# design.net
KiCad netlist of a schematic drawn in Altium Designer
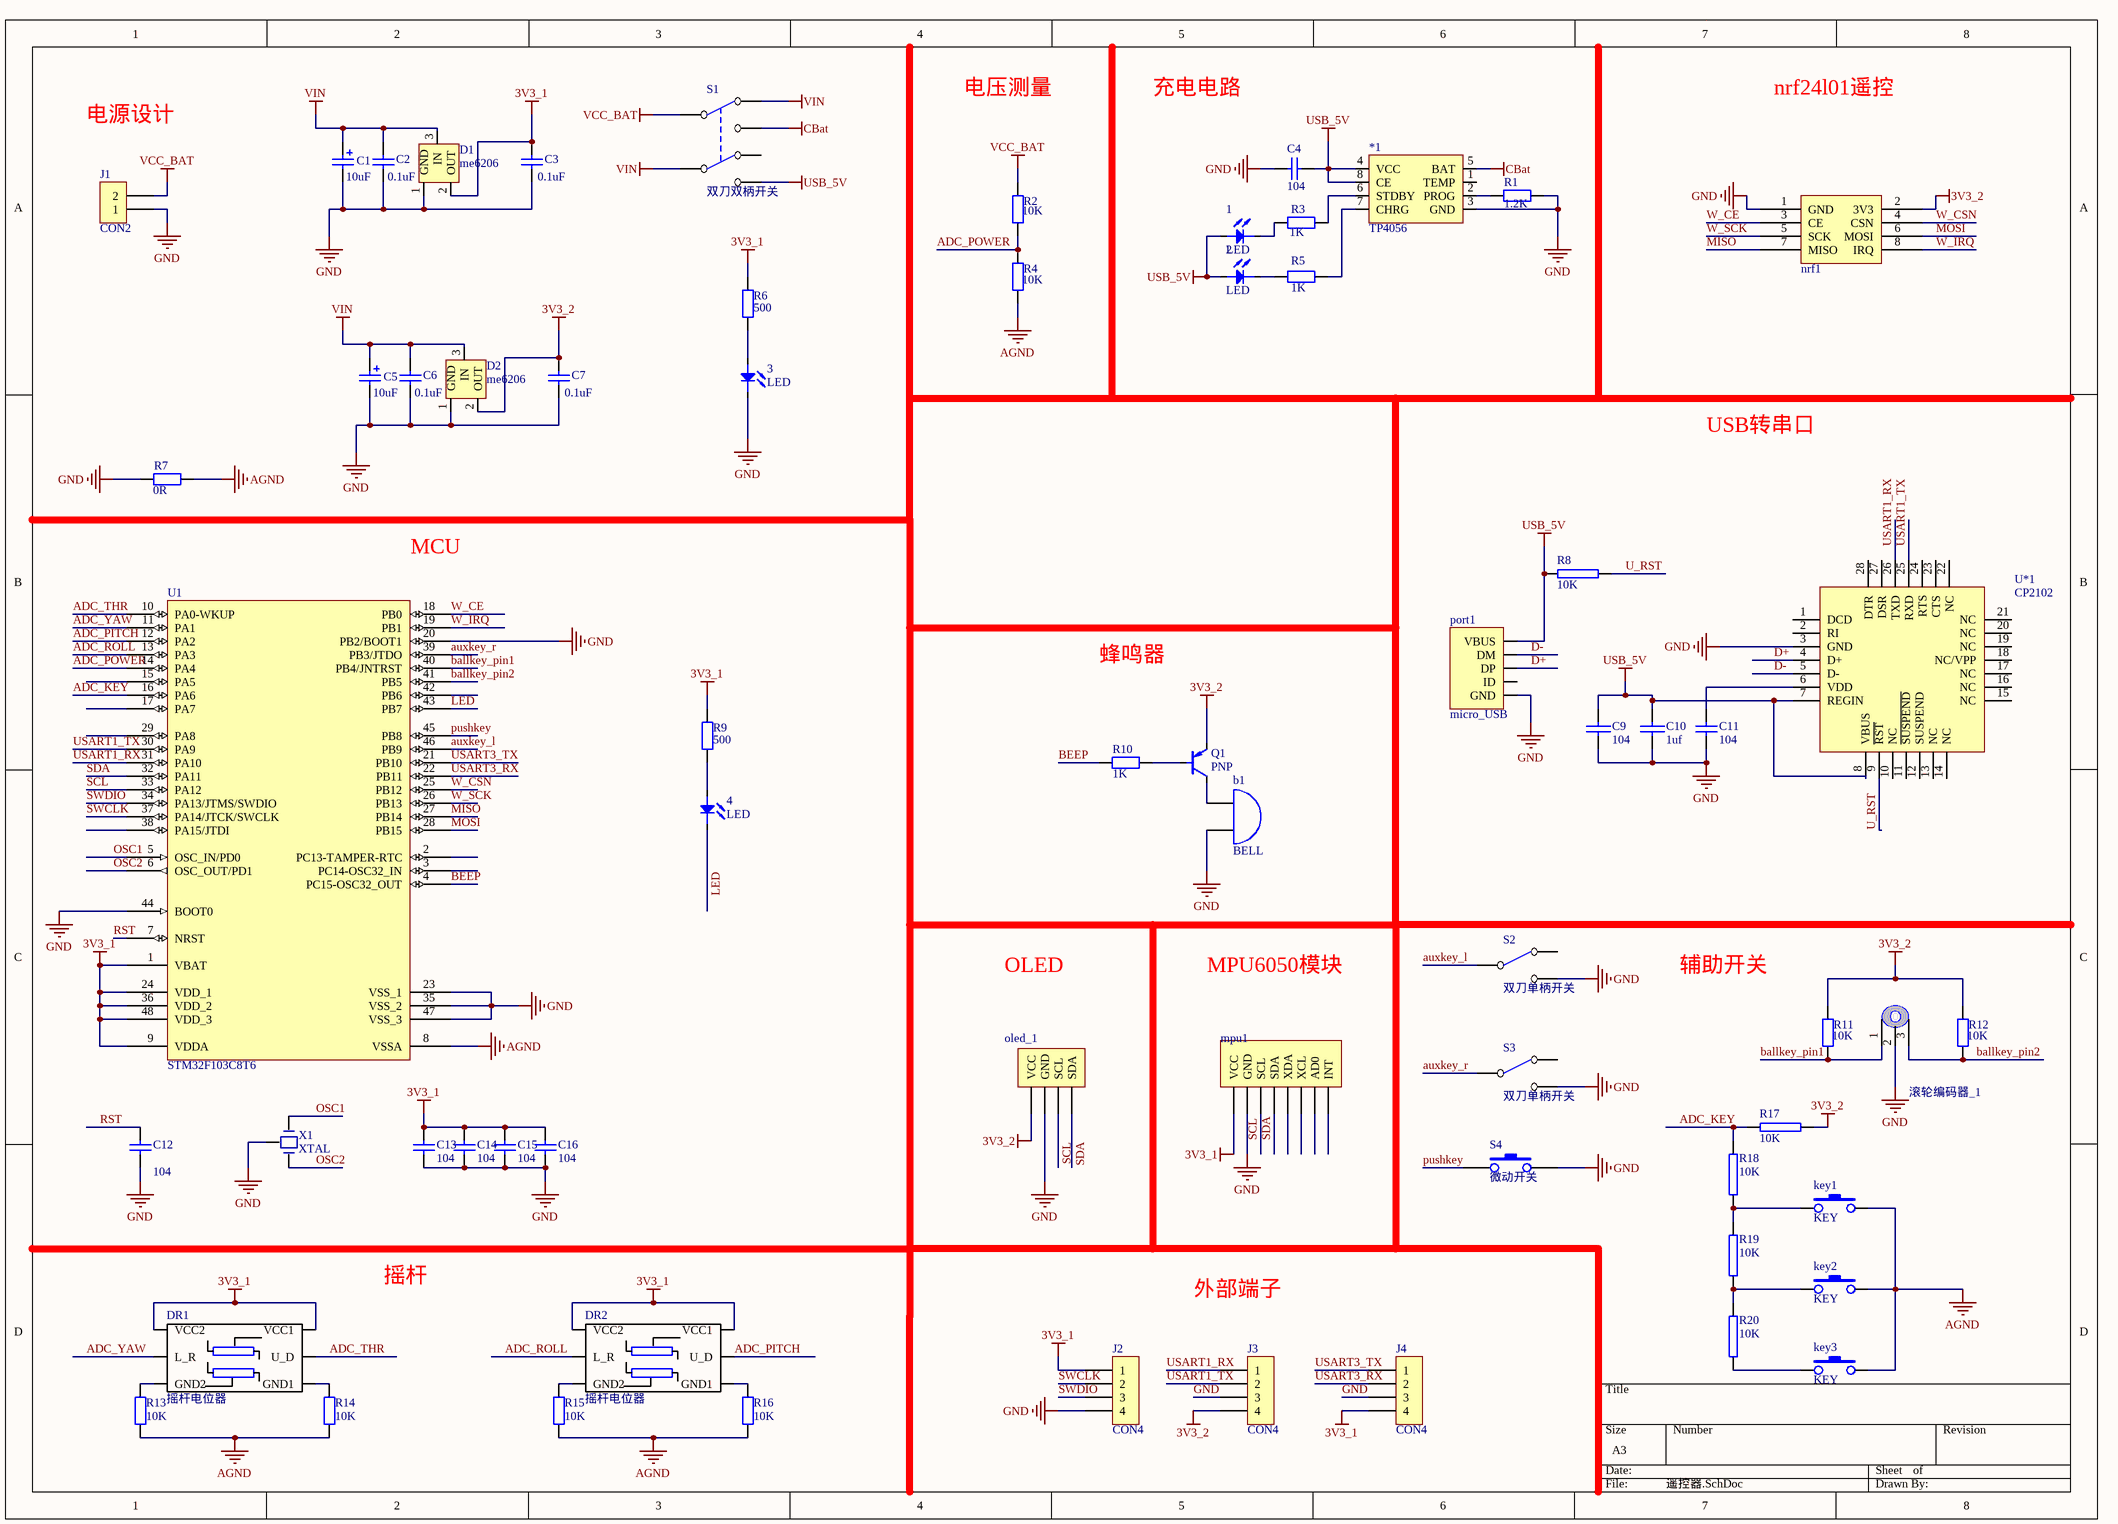
[diagram p0: 遥控器.SchDoc]

(export (version "E")
  (design (tool "Eeschema 10.0.6"))
  (components
    (comp (ref "*1") (value "TP4056") (footprint "LC-SOP-8_EP_150mil") (libsource (lib "my") (part "TP4056")))
    (comp (ref "1") (value "LED") (footprint "LC-0603_LED_S3") (libsource (lib "常用元件库") (part "LED")))
    (comp (ref "2") (value "LED") (footprint "LC-0603_LED_S3") (libsource (lib "常用元件库") (part "LED")))
    (comp (ref "3") (value "LED") (footprint "LC-0603_LED_S3") (libsource (lib "常用元件库") (part "LED")))
    (comp (ref "4") (value "LED") (footprint "LC-0603_LED_S3") (libsource (lib "常用元件库") (part "LED")))
    (comp (ref "b1") (value "BELL") (footprint "bell_d5") (libsource (lib "常用元件库") (part "BELL")))
    (comp (ref "C1")
      (value "10uF")
      (footprint "LC-0603_C")
      (description "Polarized Capacitor (Axial)")
      (fields (field (name "Comment") "Cap Pol2") (field (name "PUBLISHER") "Altium Limited"))
      (libsource (lib "Miscellaneous Devices") (part "Cap Pol2"))
    )
    (comp (ref "C2")
      (value "0.1uF")
      (footprint "LC-0603_C")
      (description "Capacitor")
      (fields (field (name "Comment") "Cap") (field (name "PUBLISHER") "Altium Limited"))
      (libsource (lib "Miscellaneous Devices") (part "Cap"))
    )
    (comp (ref "C3")
      (value "0.1uF")
      (footprint "LC-0603_C")
      (description "Capacitor")
      (fields (field (name "Comment") "Cap") (field (name "PUBLISHER") "Altium Limited"))
      (libsource (lib "Miscellaneous Devices") (part "Cap"))
    )
    (comp (ref "C4")
      (value "104")
      (footprint "LC-0603_C")
      (description "Capacitor")
      (fields (field (name "Comment") "Cap") (field (name "PUBLISHER") "Altium Limited"))
      (libsource (lib "Miscellaneous Devices") (part "Cap"))
    )
    (comp (ref "C5")
      (value "10uF")
      (footprint "LC-0603_C")
      (description "Polarized Capacitor (Axial)")
      (fields (field (name "Comment") "Cap Pol2") (field (name "PUBLISHER") "Altium Limited"))
      (libsource (lib "Miscellaneous Devices") (part "Cap Pol2"))
    )
    (comp (ref "C6")
      (value "0.1uF")
      (footprint "LC-0603_C")
      (description "Capacitor")
      (fields (field (name "Comment") "Cap") (field (name "PUBLISHER") "Altium Limited"))
      (libsource (lib "Miscellaneous Devices") (part "Cap"))
    )
    (comp (ref "C7")
      (value "0.1uF")
      (footprint "LC-0603_C")
      (description "Capacitor")
      (fields (field (name "Comment") "Cap") (field (name "PUBLISHER") "Altium Limited"))
      (libsource (lib "Miscellaneous Devices") (part "Cap"))
    )
    (comp (ref "C9") (value "104") (footprint "LC-0603_C") (libsource (lib "常用元件库") (part "CAP")))
    (comp (ref "C10") (value "1uf") (footprint "LC-0603_C") (libsource (lib "常用元件库") (part "CAP")))
    (comp (ref "C11")
      (value "104")
      (footprint "LC-0603_C")
      (description "Capacitor")
      (fields (field (name "Comment") "Cap") (field (name "PUBLISHER") "Altium Limited"))
      (libsource (lib "Miscellaneous Devices") (part "Cap"))
    )
    (comp (ref "C12")
      (value "104")
      (footprint "LC-0603_C")
      (description "Capacitor")
      (fields (field (name "Comment") "Cap") (field (name "PUBLISHER") "Altium Limited"))
      (libsource (lib "Miscellaneous Devices") (part "Cap"))
    )
    (comp (ref "C13")
      (value "104")
      (footprint "LC-0603_C")
      (description "Capacitor")
      (fields (field (name "Comment") "Cap") (field (name "PUBLISHER") "Altium Limited"))
      (libsource (lib "Miscellaneous Devices") (part "Cap"))
    )
    (comp (ref "C14")
      (value "104")
      (footprint "LC-0603_C")
      (description "Capacitor")
      (fields (field (name "Comment") "Cap") (field (name "PUBLISHER") "Altium Limited"))
      (libsource (lib "Miscellaneous Devices") (part "Cap"))
    )
    (comp (ref "C15")
      (value "104")
      (footprint "LC-0603_C")
      (description "Capacitor")
      (fields (field (name "Comment") "Cap") (field (name "PUBLISHER") "Altium Limited"))
      (libsource (lib "Miscellaneous Devices") (part "Cap"))
    )
    (comp (ref "C16")
      (value "104")
      (footprint "LC-0603_C")
      (description "Capacitor")
      (fields (field (name "Comment") "Cap") (field (name "PUBLISHER") "Altium Limited"))
      (libsource (lib "Miscellaneous Devices") (part "Cap"))
    )
    (comp (ref "D1")
      (value "me6206")
      (footprint "LC-SOT-23(SOT-23-3)")
      (libsource (lib "常用元件库") (part "me6206"))
    )
    (comp (ref "D2")
      (value "me6206")
      (footprint "LC-SOT-23(SOT-23-3)")
      (libsource (lib "常用元件库") (part "me6206"))
    )
    (comp (ref "DR1") (value "摇杆电位器") (footprint "摇杆电位器") (libsource (lib "常用元件库") (part "摇杆电位器")))
    (comp (ref "DR2") (value "摇杆电位器") (footprint "摇杆电位器") (libsource (lib "常用元件库") (part "摇杆电位器")))
    (comp (ref "J1") (value "CON2") (footprint "SIP2") (libsource (lib "常用元件库") (part "CON2")))
    (comp (ref "J2") (value "CON4") (footprint "SIP4") (libsource (lib "常用元件库") (part "CON4")))
    (comp (ref "J3") (value "CON4") (footprint "SIP4") (libsource (lib "常用元件库") (part "CON4")))
    (comp (ref "J4") (value "CON4") (footprint "SIP4") (libsource (lib "常用元件库") (part "CON4")))
    (comp (ref "key1") (value "KEY") (footprint "贴片按键6.1x3.7") (libsource (lib "常用元件库") (part "KEY")))
    (comp (ref "key2") (value "KEY") (footprint "贴片按键6.1x3.7") (libsource (lib "常用元件库") (part "KEY")))
    (comp (ref "key3") (value "KEY") (footprint "贴片按键6.1x3.7") (libsource (lib "常用元件库") (part "KEY")))
    (comp (ref "mpu1") (value "CON8") (footprint "MPU6050模块") (libsource (lib "常用元件库") (part "mpu6050模块")))
    (comp (ref "nrf1")
      (value "nrf24l01")
      (footprint "nrf模块（带天线）")
      (libsource (lib "常用元件库") (part "nrf24l01"))
    )
    (comp (ref "oled_1")
      (value "CON4")
      (footprint "oled_i2c_0.96")
      (libsource (lib "常用元件库") (part "oled_0.96_i2c"))
    )
    (comp (ref "port1")
      (value "micro_USB")
      (footprint "MICRO-USB")
      (libsource (lib "常用元件库") (part "micro_USB"))
    )
    (comp (ref "Q1") (value "PNP") (footprint "LC-SC-70-6(SOT-363)") (libsource (lib "常用元件库") (part "PNP")))
    (comp (ref "R1")
      (value "1.2K")
      (footprint "LC-0603_R")
      (description "Resistor")
      (fields (field (name "Comment") "Res2") (field (name "PUBLISHER") "Altium Limited"))
      (libsource (lib "") (part "Res2_3"))
    )
    (comp (ref "R2")
      (value "10K")
      (footprint "LC-0603_R")
      (description "Resistor")
      (fields (field (name "Comment") "Res2") (field (name "PUBLISHER") "Altium Limited"))
      (libsource (lib "") (part "Res2_1"))
    )
    (comp (ref "R3")
      (value "1K")
      (footprint "LC-0603_R")
      (description "Resistor")
      (fields (field (name "Comment") "Res2") (field (name "PUBLISHER") "Altium Limited"))
      (libsource (lib "") (part "Res2_3"))
    )
    (comp (ref "R4")
      (value "10K")
      (footprint "LC-0603_R")
      (description "Resistor")
      (fields (field (name "Comment") "Res2") (field (name "PUBLISHER") "Altium Limited"))
      (libsource (lib "") (part "Res2_1"))
    )
    (comp (ref "R5")
      (value "1K")
      (footprint "LC-0603_R")
      (description "Resistor")
      (fields (field (name "Comment") "Res2") (field (name "PUBLISHER") "Altium Limited"))
      (libsource (lib "") (part "Res2_3"))
    )
    (comp (ref "R6")
      (value "500")
      (footprint "LC-0603_R")
      (description "Resistor")
      (fields (field (name "Comment") "Res2") (field (name "PUBLISHER") "Altium Limited"))
      (libsource (lib "") (part "Res2_1"))
    )
    (comp (ref "R7")
      (value "0R")
      (footprint "LC-0603_R")
      (description "Resistor")
      (fields (field (name "Comment") "Res2") (field (name "PUBLISHER") "Altium Limited"))
      (libsource (lib "Miscellaneous Devices") (part "Res2"))
    )
    (comp (ref "R8") (value "10K") (footprint "LC-0603_R") (libsource (lib "常用元件库") (part "RES")))
    (comp (ref "R9")
      (value "500")
      (footprint "LC-0603_R")
      (description "Resistor")
      (fields (field (name "Comment") "Res2") (field (name "PUBLISHER") "Altium Limited"))
      (libsource (lib "") (part "Res2_1"))
    )
    (comp (ref "R10")
      (value "1K")
      (footprint "LC-0603_R")
      (description "Resistor")
      (fields (field (name "Comment") "Res2") (field (name "PUBLISHER") "Altium Limited"))
      (libsource (lib "") (part "Res2_3"))
    )
    (comp (ref "R11")
      (value "10K")
      (footprint "LC-0603_R")
      (description "Resistor")
      (fields (field (name "Comment") "Res2") (field (name "PUBLISHER") "Altium Limited"))
      (libsource (lib "") (part "Res2_1"))
    )
    (comp (ref "R12")
      (value "10K")
      (footprint "LC-0603_R")
      (description "Resistor")
      (fields (field (name "Comment") "Res2") (field (name "PUBLISHER") "Altium Limited"))
      (libsource (lib "") (part "Res2_1"))
    )
    (comp (ref "R13")
      (value "10K")
      (footprint "LC-0603_R")
      (description "Resistor")
      (fields (field (name "Comment") "Res2") (field (name "PUBLISHER") "Altium Limited"))
      (libsource (lib "") (part "Res2_2"))
    )
    (comp (ref "R14")
      (value "10K")
      (footprint "LC-0603_R")
      (description "Resistor")
      (fields (field (name "Comment") "Res2") (field (name "PUBLISHER") "Altium Limited"))
      (libsource (lib "") (part "Res2_2"))
    )
    (comp (ref "R15")
      (value "10K")
      (footprint "LC-0603_R")
      (description "Resistor")
      (fields (field (name "Comment") "Res2") (field (name "PUBLISHER") "Altium Limited"))
      (libsource (lib "") (part "Res2_2"))
    )
    (comp (ref "R16")
      (value "10K")
      (footprint "LC-0603_R")
      (description "Resistor")
      (fields (field (name "Comment") "Res2") (field (name "PUBLISHER") "Altium Limited"))
      (libsource (lib "") (part "Res2_2"))
    )
    (comp (ref "R17") (value "10K") (footprint "LC-0603_R") (libsource (lib "常用元件库") (part "RES")))
    (comp (ref "R18") (value "10K") (footprint "LC-0603_R") (libsource (lib "常用元件库") (part "RES")))
    (comp (ref "R19") (value "10K") (footprint "LC-0603_R") (libsource (lib "常用元件库") (part "RES")))
    (comp (ref "R20") (value "10K") (footprint "LC-0603_R") (libsource (lib "常用元件库") (part "RES")))
    (comp (ref "S1") (value "双刀双柄开关") (footprint "开关双联六脚") (libsource (lib "常用元件库") (part "双刀双柄开关")))
    (comp (ref "S2") (value "双刀单柄开关") (footprint "二段开关8x5mm") (libsource (lib "常用元件库") (part "双刀单柄开关")))
    (comp (ref "S3") (value "双刀单柄开关") (footprint "二段开关8x5mm") (libsource (lib "常用元件库") (part "双刀单柄开关")))
    (comp (ref "S4") (value "微动开关") (footprint "微动开关") (libsource (lib "常用元件库") (part "微动开关")))
    (comp (ref "U*1")
      (value "CP2102")
      (footprint "LC-QFN-28_5x5x05P")
      (description "USBtoTTL")
      (libsource (lib "常用元件库") (part "CP2102"))
    )
    (comp (ref "U1")
      (value "STM32F103C8T6")
      (footprint "LQFP48_N")
      (description "STM32 ARM-based 32-bit MCU with 64 Kbytes Flash, 48-pin LQFP, Industrial Temperature")
      (fields (field (name "PUBLISHER") "*"))
      (libsource (lib "STM32 SCH") (part "STM32F103C8T6"))
    )
    (comp (ref "X1") (value "XTAL") (footprint "三脚晶振") (libsource (lib "常用元件库") (part "XTAL_3P")))
    (comp (ref "滚轮编码器_1")
      (value "滚轮编码器_7mm")
      (footprint "滚轮编码器")
      (libsource (lib "常用元件库") (part "滚轮编码器_7mm"))
    )
  )
  (nets
    (net (code "1") (name "/ADC_KEY") (class "Default")
      (node (ref "R17") (pin "2") (pinfunction "2_2") (pintype "passive"))
      (node (ref "R18") (pin "2") (pinfunction "2_2") (pintype "passive"))
      (node (ref "U1") (pin "16") (pinfunction "PA6_16") (pintype "bidirectional"))
    )
    (net (code "2") (name "/ADC_PITCH") (class "Default")
      (node (ref "DR2") (pin "2") (pinfunction "U_D_2") (pintype "passive"))
      (node (ref "U1") (pin "12") (pinfunction "PA2_12") (pintype "bidirectional"))
    )
    (net (code "3") (name "/ADC_POWER") (class "Default")
      (node (ref "R2") (pin "1") (pinfunction "1_1") (pintype "passive"))
      (node (ref "R4") (pin "2") (pinfunction "2_2") (pintype "passive"))
      (node (ref "U1") (pin "14") (pinfunction "PA4_14") (pintype "bidirectional"))
    )
    (net (code "4") (name "/ADC_ROLL") (class "Default")
      (node (ref "DR2") (pin "5") (pinfunction "L_R_5") (pintype "passive"))
      (node (ref "U1") (pin "13") (pinfunction "PA3_13") (pintype "bidirectional"))
    )
    (net (code "5") (name "/ADC_THR") (class "Default")
      (node (ref "DR1") (pin "2") (pinfunction "U_D_2") (pintype "passive"))
      (node (ref "U1") (pin "10") (pinfunction "PA0-WKUP_10") (pintype "bidirectional"))
    )
    (net (code "6") (name "/ADC_YAW") (class "Default")
      (node (ref "DR1") (pin "5") (pinfunction "L_R_5") (pintype "passive"))
      (node (ref "U1") (pin "11") (pinfunction "PA1_11") (pintype "bidirectional"))
    )
    (net (code "7") (name "/BEEP") (class "Default")
      (node (ref "R10") (pin "2") (pinfunction "2_2") (pintype "passive"))
      (node (ref "U1") (pin "4") (pinfunction "PC15-OSC32_OUT_4") (pintype "bidirectional"))
    )
    (net (code "8") (name "/D+") (class "Default")
      (node (ref "U*1") (pin "4") (pinfunction "D+_4") (pintype "passive"))
      (node (ref "port1") (pin "3") (pinfunction "DP_3") (pintype "passive"))
    )
    (net (code "9") (name "/D-") (class "Default")
      (node (ref "U*1") (pin "5") (pinfunction "D-_5") (pintype "passive"))
      (node (ref "port1") (pin "2") (pinfunction "DM_2") (pintype "passive"))
    )
    (net (code "10") (name "/LED") (class "Default")
      (node (ref "4") (pin "K") (pintype "passive"))
      (node (ref "U1") (pin "43") (pinfunction "PB7_43") (pintype "bidirectional"))
    )
    (net (code "11") (name "/MISO") (class "Default")
      (node (ref "U1") (pin "27") (pinfunction "PB14_27") (pintype "bidirectional"))
      (node (ref "nrf1") (pin "7") (pinfunction "MISO_7") (pintype "passive"))
    )
    (net (code "12") (name "/MOSI") (class "Default")
      (node (ref "U1") (pin "28") (pinfunction "PB15_28") (pintype "bidirectional"))
      (node (ref "nrf1") (pin "6") (pinfunction "MOSI_6") (pintype "passive"))
    )
    (net (code "13") (name "/OSC1") (class "Default")
      (node (ref "U1") (pin "5") (pinfunction "OSC_IN/PD0_5") (pintype "input"))
      (node (ref "X1") (pin "1") (pinfunction "1_1") (pintype "passive"))
    )
    (net (code "14") (name "/OSC2") (class "Default")
      (node (ref "U1") (pin "6") (pinfunction "OSC_OUT/PD1_6") (pintype "output"))
      (node (ref "X1") (pin "2") (pinfunction "2_2") (pintype "passive"))
    )
    (net (code "15") (name "/RST") (class "Default")
      (node (ref "C12") (pin "1") (pinfunction "1_1") (pintype "passive"))
      (node (ref "U1") (pin "7") (pinfunction "NRST_7") (pintype "bidirectional"))
    )
    (net (code "16") (name "/SCL") (class "Default")
      (node (ref "U1") (pin "33") (pinfunction "PA12_33") (pintype "bidirectional"))
      (node (ref "mpu1") (pin "3") (pinfunction "SCL_3") (pintype "passive"))
      (node (ref "oled_1") (pin "3") (pinfunction "SCL_3") (pintype "passive"))
    )
    (net (code "17") (name "/SDA") (class "Default")
      (node (ref "U1") (pin "32") (pinfunction "PA11_32") (pintype "bidirectional"))
      (node (ref "mpu1") (pin "4") (pinfunction "SDA_4") (pintype "passive"))
      (node (ref "oled_1") (pin "4") (pinfunction "SDA_4") (pintype "passive"))
    )
    (net (code "18") (name "/SWCLK") (class "Default")
      (node (ref "J2") (pin "2") (pinfunction "2_2") (pintype "passive"))
      (node (ref "U1") (pin "37") (pinfunction "PA14/JTCK/SWCLK_37") (pintype "bidirectional"))
    )
    (net (code "19") (name "/SWDIO") (class "Default")
      (node (ref "J2") (pin "3") (pinfunction "3_3") (pintype "passive"))
      (node (ref "U1") (pin "34") (pinfunction "PA13/JTMS/SWDIO_34") (pintype "bidirectional"))
    )
    (net (code "20") (name "/USART1_RX") (class "Default")
      (node (ref "J3") (pin "1") (pinfunction "1_1") (pintype "passive"))
      (node (ref "U*1") (pin "26") (pinfunction "TXD_26") (pintype "passive"))
      (node (ref "U1") (pin "31") (pinfunction "PA10_31") (pintype "bidirectional"))
    )
    (net (code "21") (name "/USART1_TX") (class "Default")
      (node (ref "J3") (pin "2") (pinfunction "2_2") (pintype "passive"))
      (node (ref "U*1") (pin "25") (pinfunction "RXD_25") (pintype "passive"))
      (node (ref "U1") (pin "30") (pinfunction "PA9_30") (pintype "bidirectional"))
    )
    (net (code "22") (name "/USART3_RX") (class "Default")
      (node (ref "J4") (pin "2") (pinfunction "2_2") (pintype "passive"))
      (node (ref "U1") (pin "22") (pinfunction "PB11_22") (pintype "bidirectional"))
    )
    (net (code "23") (name "/USART3_TX") (class "Default")
      (node (ref "J4") (pin "1") (pinfunction "1_1") (pintype "passive"))
      (node (ref "U1") (pin "21") (pinfunction "PB10_21") (pintype "bidirectional"))
    )
    (net (code "24") (name "/U_RST") (class "Default")
      (node (ref "R8") (pin "2") (pinfunction "2_2") (pintype "passive"))
      (node (ref "U*1") (pin "9") (pinfunction "~{RST}_9") (pintype "passive"))
    )
    (net (code "25") (name "/W_CE") (class "Default")
      (node (ref "U1") (pin "18") (pinfunction "PB0_18") (pintype "bidirectional"))
      (node (ref "nrf1") (pin "3") (pinfunction "CE_3") (pintype "passive"))
    )
    (net (code "26") (name "/W_CSN") (class "Default")
      (node (ref "U1") (pin "25") (pinfunction "PB12_25") (pintype "bidirectional"))
      (node (ref "nrf1") (pin "4") (pinfunction "CSN_4") (pintype "passive"))
    )
    (net (code "27") (name "/W_IRQ") (class "Default")
      (node (ref "U1") (pin "19") (pinfunction "PB1_19") (pintype "bidirectional"))
      (node (ref "nrf1") (pin "8") (pinfunction "IRQ_8") (pintype "passive"))
    )
    (net (code "28") (name "/W_SCK") (class "Default")
      (node (ref "U1") (pin "26") (pinfunction "PB13_26") (pintype "bidirectional"))
      (node (ref "nrf1") (pin "5") (pinfunction "SCK_5") (pintype "passive"))
    )
    (net (code "29") (name "/auxkey_l") (class "Default")
      (node (ref "S2") (pin "1") (pinfunction "COMMON_1") (pintype "passive"))
      (node (ref "U1") (pin "46") (pinfunction "PB9_46") (pintype "bidirectional"))
    )
    (net (code "30") (name "/auxkey_r") (class "Default")
      (node (ref "S3") (pin "1") (pinfunction "COMMON_1") (pintype "passive"))
      (node (ref "U1") (pin "39") (pinfunction "PB3/JTDO_39") (pintype "bidirectional"))
    )
    (net (code "31") (name "/ballkey_pin1") (class "Default")
      (node (ref "R11") (pin "1") (pinfunction "1_1") (pintype "passive"))
      (node (ref "U1") (pin "40") (pinfunction "PB4/JNTRST_40") (pintype "bidirectional"))
      (node (ref "滚轮编码器_1") (pin "1") (pintype "passive"))
    )
    (net (code "32") (name "/ballkey_pin2") (class "Default")
      (node (ref "R12") (pin "1") (pinfunction "1_1") (pintype "passive"))
      (node (ref "U1") (pin "41") (pinfunction "PB5_41") (pintype "bidirectional"))
      (node (ref "滚轮编码器_1") (pin "3") (pintype "passive"))
    )
    (net (code "33") (name "/pushkey") (class "Default")
      (node (ref "S4") (pin "1") (pinfunction "1_1") (pintype "passive"))
      (node (ref "U1") (pin "45") (pinfunction "PB8_45") (pintype "bidirectional"))
    )
    (net (code "34") (name "3V3_1") (class "Default")
      (node (ref "C13") (pin "1") (pinfunction "1_1") (pintype "passive"))
      (node (ref "C14") (pin "1") (pinfunction "1_1") (pintype "passive"))
      (node (ref "C15") (pin "1") (pinfunction "1_1") (pintype "passive"))
      (node (ref "C16") (pin "1") (pinfunction "1_1") (pintype "passive"))
      (node (ref "C3") (pin "1") (pinfunction "1_1") (pintype "passive"))
      (node (ref "D1") (pin "2") (pinfunction "OUT_2") (pintype "passive"))
      (node (ref "DR1") (pin "1") (pinfunction "VCC1_1") (pintype "passive"))
      (node (ref "DR1") (pin "4") (pinfunction "VCC2_4") (pintype "passive"))
      (node (ref "DR2") (pin "1") (pinfunction "VCC1_1") (pintype "passive"))
      (node (ref "DR2") (pin "4") (pinfunction "VCC2_4") (pintype "passive"))
      (node (ref "J2") (pin "1") (pinfunction "1_1") (pintype "passive"))
      (node (ref "J4") (pin "4") (pinfunction "4_4") (pintype "passive"))
      (node (ref "R6") (pin "2") (pinfunction "2_2") (pintype "passive"))
      (node (ref "R9") (pin "2") (pinfunction "2_2") (pintype "passive"))
      (node (ref "U1") (pin "1") (pinfunction "VBAT_1") (pintype "power_in"))
      (node (ref "U1") (pin "24") (pinfunction "VDD_1_24") (pintype "power_in"))
      (node (ref "U1") (pin "36") (pinfunction "VDD_2_36") (pintype "power_in"))
      (node (ref "U1") (pin "48") (pinfunction "VDD_3_48") (pintype "power_in"))
      (node (ref "U1") (pin "9") (pinfunction "VDDA_9") (pintype "power_in"))
      (node (ref "mpu1") (pin "1") (pinfunction "VCC_1") (pintype "passive"))
    )
    (net (code "35") (name "3V3_2") (class "Default")
      (node (ref "C7") (pin "1") (pinfunction "1_1") (pintype "passive"))
      (node (ref "D2") (pin "2") (pinfunction "OUT_2") (pintype "passive"))
      (node (ref "J3") (pin "4") (pinfunction "4_4") (pintype "passive"))
      (node (ref "Q1") (pin "1") (pinfunction "e_1") (pintype "passive"))
      (node (ref "R11") (pin "2") (pinfunction "2_2") (pintype "passive"))
      (node (ref "R12") (pin "2") (pinfunction "2_2") (pintype "passive"))
      (node (ref "R17") (pin "1") (pinfunction "1_1") (pintype "passive"))
      (node (ref "nrf1") (pin "2") (pinfunction "3V3_2") (pintype "passive"))
      (node (ref "oled_1") (pin "1") (pinfunction "VCC_1") (pintype "passive"))
    )
    (net (code "36") (name "AGND") (class "Default")
      (node (ref "R13") (pin "2") (pinfunction "2_2") (pintype "passive"))
      (node (ref "R14") (pin "2") (pinfunction "2_2") (pintype "passive"))
      (node (ref "R15") (pin "2") (pinfunction "2_2") (pintype "passive"))
      (node (ref "R16") (pin "2") (pinfunction "2_2") (pintype "passive"))
      (node (ref "R4") (pin "1") (pinfunction "1_1") (pintype "passive"))
      (node (ref "R7") (pin "2") (pinfunction "2_2") (pintype "passive"))
      (node (ref "U1") (pin "8") (pinfunction "VSSA_8") (pintype "power_in"))
      (node (ref "key1") (pin "2") (pinfunction "2_2") (pintype "passive"))
      (node (ref "key2") (pin "2") (pinfunction "2_2") (pintype "passive"))
      (node (ref "key3") (pin "2") (pinfunction "2_2") (pintype "passive"))
    )
    (net (code "37") (name "CBat") (class "Default")
      (node (ref "*1") (pin "5") (pinfunction "BAT_5") (pintype "passive"))
      (node (ref "S1") (pin "3") (pinfunction "NO1_3") (pintype "passive"))
    )
    (net (code "38") (name "GND") (class "Default")
      (node (ref "*1") (pin "3") (pinfunction "GND_3") (pintype "passive"))
      (node (ref "3") (pin "K") (pintype "passive"))
      (node (ref "C1") (pin "2") (pinfunction "2_2") (pintype "passive"))
      (node (ref "C10") (pin "1") (pinfunction "1_1") (pintype "passive"))
      (node (ref "C11") (pin "1") (pinfunction "1_1") (pintype "passive"))
      (node (ref "C12") (pin "2") (pinfunction "2_2") (pintype "passive"))
      (node (ref "C13") (pin "2") (pinfunction "2_2") (pintype "passive"))
      (node (ref "C14") (pin "2") (pinfunction "2_2") (pintype "passive"))
      (node (ref "C15") (pin "2") (pinfunction "2_2") (pintype "passive"))
      (node (ref "C16") (pin "2") (pinfunction "2_2") (pintype "passive"))
      (node (ref "C2") (pin "2") (pinfunction "2_2") (pintype "passive"))
      (node (ref "C3") (pin "2") (pinfunction "2_2") (pintype "passive"))
      (node (ref "C4") (pin "2") (pinfunction "2_2") (pintype "passive"))
      (node (ref "C5") (pin "2") (pinfunction "2_2") (pintype "passive"))
      (node (ref "C6") (pin "2") (pinfunction "2_2") (pintype "passive"))
      (node (ref "C7") (pin "2") (pinfunction "2_2") (pintype "passive"))
      (node (ref "C9") (pin "2") (pinfunction "2_2") (pintype "passive"))
      (node (ref "D1") (pin "1") (pinfunction "GND_1") (pintype "passive"))
      (node (ref "D2") (pin "1") (pinfunction "GND_1") (pintype "passive"))
      (node (ref "J1") (pin "1") (pinfunction "1_1") (pintype "passive"))
      (node (ref "J2") (pin "4") (pinfunction "4_4") (pintype "passive"))
      (node (ref "J3") (pin "3") (pinfunction "3_3") (pintype "passive"))
      (node (ref "J4") (pin "3") (pinfunction "3_3") (pintype "passive"))
      (node (ref "R1") (pin "1") (pinfunction "1_1") (pintype "passive"))
      (node (ref "R7") (pin "1") (pinfunction "1_1") (pintype "passive"))
      (node (ref "S2") (pin "3") (pinfunction "NO_3") (pintype "passive"))
      (node (ref "S3") (pin "3") (pinfunction "NO_3") (pintype "passive"))
      (node (ref "S4") (pin "2") (pinfunction "2_2") (pintype "passive"))
      (node (ref "U*1") (pin "3") (pinfunction "GND_3") (pintype "passive"))
      (node (ref "U1") (pin "20") (pinfunction "PB2/BOOT1_20") (pintype "bidirectional"))
      (node (ref "U1") (pin "23") (pinfunction "VSS_1_23") (pintype "power_in"))
      (node (ref "U1") (pin "35") (pinfunction "VSS_2_35") (pintype "power_in"))
      (node (ref "U1") (pin "44") (pinfunction "BOOT0_44") (pintype "input"))
      (node (ref "U1") (pin "47") (pinfunction "VSS_3_47") (pintype "power_in"))
      (node (ref "X1") (pin "3") (pinfunction "3_3") (pintype "passive"))
      (node (ref "b1") (pin "2") (pinfunction "2_2") (pintype "passive"))
      (node (ref "mpu1") (pin "2") (pinfunction "GND_2") (pintype "passive"))
      (node (ref "nrf1") (pin "1") (pinfunction "GND_1") (pintype "passive"))
      (node (ref "oled_1") (pin "2") (pinfunction "GND_2") (pintype "passive"))
      (node (ref "port1") (pin "5") (pinfunction "GND_5") (pintype "passive"))
      (node (ref "滚轮编码器_1") (pin "2") (pintype "passive"))
    )
    (net (code "39") (name "Net-(*1-CHRG)") (class "Default")
      (node (ref "*1") (pin "7") (pinfunction "CHRG_7") (pintype "passive"))
      (node (ref "R5") (pin "1") (pinfunction "1_1") (pintype "passive"))
    )
    (net (code "40") (name "Net-(*1-PROG)") (class "Default")
      (node (ref "*1") (pin "2") (pinfunction "PROG_2") (pintype "passive"))
      (node (ref "R1") (pin "2") (pinfunction "2_2") (pintype "passive"))
    )
    (net (code "41") (name "Net-(*1-STDBY)") (class "Default")
      (node (ref "*1") (pin "6") (pinfunction "STDBY_6") (pintype "passive"))
      (node (ref "R3") (pin "1") (pinfunction "1_1") (pintype "passive"))
    )
    (net (code "42") (name "Net-(1-PadK)") (class "Default")
      (node (ref "1") (pin "K") (pintype "passive"))
      (node (ref "R3") (pin "2") (pinfunction "2_2") (pintype "passive"))
    )
    (net (code "43") (name "Net-(2-PadK)") (class "Default")
      (node (ref "2") (pin "K") (pintype "passive"))
      (node (ref "R5") (pin "2") (pinfunction "2_2") (pintype "passive"))
    )
    (net (code "44") (name "Net-(3-PadA)") (class "Default")
      (node (ref "3") (pin "A") (pintype "passive"))
      (node (ref "R6") (pin "1") (pinfunction "1_1") (pintype "passive"))
    )
    (net (code "45") (name "Net-(4-PadA)") (class "Default")
      (node (ref "4") (pin "A") (pintype "passive"))
      (node (ref "R9") (pin "1") (pinfunction "1_1") (pintype "passive"))
    )
    (net (code "46") (name "Net-(DR1-GND1)") (class "Default")
      (node (ref "DR1") (pin "3") (pinfunction "GND1_3") (pintype "passive"))
      (node (ref "R14") (pin "1") (pinfunction "1_1") (pintype "passive"))
    )
    (net (code "47") (name "Net-(DR1-GND2)") (class "Default")
      (node (ref "DR1") (pin "6") (pinfunction "GND2_6") (pintype "passive"))
      (node (ref "R13") (pin "1") (pinfunction "1_1") (pintype "passive"))
    )
    (net (code "48") (name "Net-(DR2-GND1)") (class "Default")
      (node (ref "DR2") (pin "3") (pinfunction "GND1_3") (pintype "passive"))
      (node (ref "R16") (pin "1") (pinfunction "1_1") (pintype "passive"))
    )
    (net (code "49") (name "Net-(DR2-GND2)") (class "Default")
      (node (ref "DR2") (pin "6") (pinfunction "GND2_6") (pintype "passive"))
      (node (ref "R15") (pin "1") (pinfunction "1_1") (pintype "passive"))
    )
    (net (code "50") (name "Net-(Q1-b)") (class "Default")
      (node (ref "Q1") (pin "2") (pinfunction "b_2") (pintype "passive"))
      (node (ref "R10") (pin "1") (pinfunction "1_1") (pintype "passive"))
    )
    (net (code "51") (name "Net-(Q1-c)") (class "Default")
      (node (ref "Q1") (pin "6") (pinfunction "c_6") (pintype "passive"))
      (node (ref "b1") (pin "1") (pinfunction "1_1") (pintype "passive"))
    )
    (net (code "52") (name "Net-(R18-Pad1)") (class "Default")
      (node (ref "R18") (pin "1") (pinfunction "1_1") (pintype "passive"))
      (node (ref "R19") (pin "2") (pinfunction "2_2") (pintype "passive"))
      (node (ref "key1") (pin "1") (pinfunction "1_1") (pintype "passive"))
    )
    (net (code "53") (name "Net-(R19-Pad1)") (class "Default")
      (node (ref "R19") (pin "1") (pinfunction "1_1") (pintype "passive"))
      (node (ref "R20") (pin "2") (pinfunction "2_2") (pintype "passive"))
      (node (ref "key2") (pin "1") (pinfunction "1_1") (pintype "passive"))
    )
    (net (code "54") (name "Net-(R20-Pad1)") (class "Default")
      (node (ref "R20") (pin "1") (pinfunction "1_1") (pintype "passive"))
      (node (ref "key3") (pin "1") (pinfunction "1_1") (pintype "passive"))
    )
    (net (code "55") (name "Net-(U*1-VDD)") (class "Default")
      (node (ref "C11") (pin "2") (pinfunction "2_2") (pintype "passive"))
      (node (ref "U*1") (pin "6") (pinfunction "VDD_6") (pintype "passive"))
    )
    (net (code "56") (name "USB_5V") (class "Default")
      (node (ref "*1") (pin "4") (pinfunction "VCC_4") (pintype "passive"))
      (node (ref "*1") (pin "8") (pinfunction "CE_8") (pintype "passive"))
      (node (ref "1") (pin "A") (pintype "passive"))
      (node (ref "2") (pin "A") (pintype "passive"))
      (node (ref "C10") (pin "2") (pinfunction "2_2") (pintype "passive"))
      (node (ref "C4") (pin "1") (pinfunction "1_1") (pintype "passive"))
      (node (ref "C9") (pin "1") (pinfunction "1_1") (pintype "passive"))
      (node (ref "R8") (pin "1") (pinfunction "1_1") (pintype "passive"))
      (node (ref "S1") (pin "6") (pinfunction "NO2_6") (pintype "passive"))
      (node (ref "U*1") (pin "7") (pinfunction "REGIN_7") (pintype "passive"))
      (node (ref "U*1") (pin "8") (pinfunction "VBUS_8") (pintype "passive"))
      (node (ref "port1") (pin "1") (pinfunction "VBUS_1") (pintype "passive"))
    )
    (net (code "57") (name "VCC_BAT") (class "Default")
      (node (ref "J1") (pin "2") (pinfunction "2_2") (pintype "passive"))
      (node (ref "R2") (pin "2") (pinfunction "2_2") (pintype "passive"))
      (node (ref "S1") (pin "1") (pinfunction "COMMON1_1") (pintype "passive"))
    )
    (net (code "58") (name "VIN") (class "Default")
      (node (ref "C1") (pin "1") (pinfunction "1_1") (pintype "passive"))
      (node (ref "C2") (pin "1") (pinfunction "1_1") (pintype "passive"))
      (node (ref "C5") (pin "1") (pinfunction "1_1") (pintype "passive"))
      (node (ref "C6") (pin "1") (pinfunction "1_1") (pintype "passive"))
      (node (ref "D1") (pin "3") (pinfunction "IN_3") (pintype "passive"))
      (node (ref "D2") (pin "3") (pinfunction "IN_3") (pintype "passive"))
      (node (ref "S1") (pin "2") (pinfunction "NC1_2") (pintype "passive"))
      (node (ref "S1") (pin "5") (pinfunction "COMMON2_5") (pintype "passive"))
    )
    (net (code "59") (name "unconnected-(*1-TEMP-Pad1)") (class "Default")
      (node (ref "*1") (pin "1") (pinfunction "TEMP_1") (pintype "passive"))
    )
    (net (code "60") (name "unconnected-(S1-NC2-Pad4)") (class "Default")
      (node (ref "S1") (pin "4") (pinfunction "NC2_4") (pintype "passive"))
    )
    (net (code "61") (name "unconnected-(S2-NC-Pad2)") (class "Default")
      (node (ref "S2") (pin "2") (pinfunction "NC_2") (pintype "passive"))
    )
    (net (code "62") (name "unconnected-(S3-NC-Pad2)") (class "Default")
      (node (ref "S3") (pin "2") (pinfunction "NC_2") (pintype "passive"))
    )
    (net (code "63") (name "unconnected-(U*1-CTS-Pad23)") (class "Default")
      (node (ref "U*1") (pin "23") (pinfunction "CTS_23") (pintype "passive"))
    )
    (net (code "64") (name "unconnected-(U*1-DCD-Pad1)") (class "Default")
      (node (ref "U*1") (pin "1") (pinfunction "DCD_1") (pintype "passive"))
    )
    (net (code "65") (name "unconnected-(U*1-DSR-Pad27)") (class "Default")
      (node (ref "U*1") (pin "27") (pinfunction "DSR_27") (pintype "passive"))
    )
    (net (code "66") (name "unconnected-(U*1-DTR-Pad28)") (class "Default")
      (node (ref "U*1") (pin "28") (pinfunction "DTR_28") (pintype "passive"))
    )
    (net (code "67") (name "unconnected-(U*1-NC-Pad10)") (class "Default")
      (node (ref "U*1") (pin "10") (pinfunction "NC_10") (pintype "passive"))
    )
    (net (code "68") (name "unconnected-(U*1-NC-Pad13)") (class "Default")
      (node (ref "U*1") (pin "13") (pinfunction "NC_13") (pintype "passive"))
    )
    (net (code "69") (name "unconnected-(U*1-NC-Pad14)") (class "Default")
      (node (ref "U*1") (pin "14") (pinfunction "NC_14") (pintype "passive"))
    )
    (net (code "70") (name "unconnected-(U*1-NC-Pad15)") (class "Default")
      (node (ref "U*1") (pin "15") (pinfunction "NC_15") (pintype "passive"))
    )
    (net (code "71") (name "unconnected-(U*1-NC-Pad16)") (class "Default")
      (node (ref "U*1") (pin "16") (pinfunction "NC_16") (pintype "passive"))
    )
    (net (code "72") (name "unconnected-(U*1-NC-Pad17)") (class "Default")
      (node (ref "U*1") (pin "17") (pinfunction "NC_17") (pintype "passive"))
    )
    (net (code "73") (name "unconnected-(U*1-NC-Pad19)") (class "Default")
      (node (ref "U*1") (pin "19") (pinfunction "NC_19") (pintype "passive"))
    )
    (net (code "74") (name "unconnected-(U*1-NC-Pad20)") (class "Default")
      (node (ref "U*1") (pin "20") (pinfunction "NC_20") (pintype "passive"))
    )
    (net (code "75") (name "unconnected-(U*1-NC-Pad21)") (class "Default")
      (node (ref "U*1") (pin "21") (pinfunction "NC_21") (pintype "passive"))
    )
    (net (code "76") (name "unconnected-(U*1-NC-Pad22)") (class "Default")
      (node (ref "U*1") (pin "22") (pinfunction "NC_22") (pintype "passive"))
    )
    (net (code "77") (name "unconnected-(U*1-NC{slash}VPP-Pad18)") (class "Default")
      (node (ref "U*1") (pin "18") (pinfunction "NC/VPP_18") (pintype "passive"))
    )
    (net (code "78") (name "unconnected-(U*1-RI-Pad2)") (class "Default")
      (node (ref "U*1") (pin "2") (pinfunction "RI_2") (pintype "passive"))
    )
    (net (code "79") (name "unconnected-(U*1-RTS-Pad24)") (class "Default")
      (node (ref "U*1") (pin "24") (pinfunction "RTS_24") (pintype "passive"))
    )
    (net (code "80") (name "unconnected-(U*1-SUSPEND-Pad12)") (class "Default")
      (node (ref "U*1") (pin "12") (pinfunction "SUSPEND_12") (pintype "passive"))
    )
    (net (code "81") (name "unconnected-(U*1-~{SUSPEND}-Pad11)") (class "Default")
      (node (ref "U*1") (pin "11") (pinfunction "~{SUSPEND}_11") (pintype "passive"))
    )
    (net (code "82") (name "unconnected-(U1-PA5-Pad15)") (class "Default")
      (node (ref "U1") (pin "15") (pinfunction "PA5_15") (pintype "bidirectional"))
    )
    (net (code "83") (name "unconnected-(U1-PA7-Pad17)") (class "Default")
      (node (ref "U1") (pin "17") (pinfunction "PA7_17") (pintype "bidirectional"))
    )
    (net (code "84") (name "unconnected-(U1-PA8-Pad29)") (class "Default")
      (node (ref "U1") (pin "29") (pinfunction "PA8_29") (pintype "bidirectional"))
    )
    (net (code "85") (name "unconnected-(U1-PA15{slash}JTDI-Pad38)") (class "Default")
      (node (ref "U1") (pin "38") (pinfunction "PA15/JTDI_38") (pintype "bidirectional"))
    )
    (net (code "86") (name "unconnected-(U1-PB6-Pad42)") (class "Default")
      (node (ref "U1") (pin "42") (pinfunction "PB6_42") (pintype "bidirectional"))
    )
    (net (code "87") (name "unconnected-(U1-PC13-TAMPER-RTC-Pad2)") (class "Default")
      (node (ref "U1") (pin "2") (pinfunction "PC13-TAMPER-RTC_2") (pintype "bidirectional"))
    )
    (net (code "88") (name "unconnected-(U1-PC14-OSC32_IN-Pad3)") (class "Default")
      (node (ref "U1") (pin "3") (pinfunction "PC14-OSC32_IN_3") (pintype "bidirectional"))
    )
    (net (code "89") (name "unconnected-(mpu1-AD0-Pad7)") (class "Default")
      (node (ref "mpu1") (pin "7") (pinfunction "AD0_7") (pintype "passive"))
    )
    (net (code "90") (name "unconnected-(mpu1-INT-Pad8)") (class "Default")
      (node (ref "mpu1") (pin "8") (pinfunction "INT_8") (pintype "passive"))
    )
    (net (code "91") (name "unconnected-(mpu1-XCL-Pad6)") (class "Default")
      (node (ref "mpu1") (pin "6") (pinfunction "XCL_6") (pintype "passive"))
    )
    (net (code "92") (name "unconnected-(mpu1-XDA-Pad5)") (class "Default")
      (node (ref "mpu1") (pin "5") (pinfunction "XDA_5") (pintype "passive"))
    )
    (net (code "93") (name "unconnected-(port1-ID-Pad4)") (class "Default")
      (node (ref "port1") (pin "4") (pinfunction "ID_4") (pintype "passive"))
    )
  )
)
